# design.net
KiCad netlist of a schematic drawn in Altium Designer
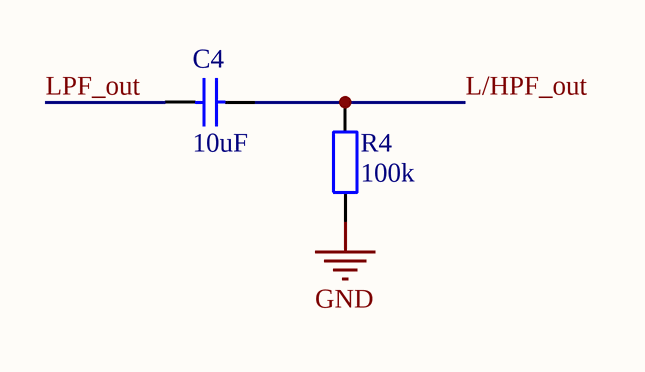
[diagram p0: 无源高通.SchDoc]

(export (version "E")
  (design (tool "Eeschema 10.0.6"))
  (components
    (comp (ref "C4")
      (value "10uF")
      (footprint "LC-0805_C")
      (description "100nF��0805��50V,+/-10%")
      (libsource (lib "ECG") (part "Cap"))
    )
    (comp (ref "R4")
      (value "100k")
      (footprint "LC-0805_R")
      (description "10k��,0805,��5%")
      (libsource (lib "ECG") (part "R"))
    )
  )
  (nets
    (net (code "1") (name "/LPF_out") (class "Default")
      (node (ref "C4") (pin "1") (pinfunction "1_1") (pintype "passive"))
    )
    (net (code "2") (name "/L{slash}HPF_out") (class "Default")
      (node (ref "C4") (pin "2") (pinfunction "2_2") (pintype "passive"))
      (node (ref "R4") (pin "2") (pintype "passive"))
    )
    (net (code "3") (name "GND") (class "Default") (node (ref "R4") (pin "1") (pintype "passive")))
  )
)
